# FT232-Breakout-v1.net
KiCad netlist of a schematic drawn in EAGLE
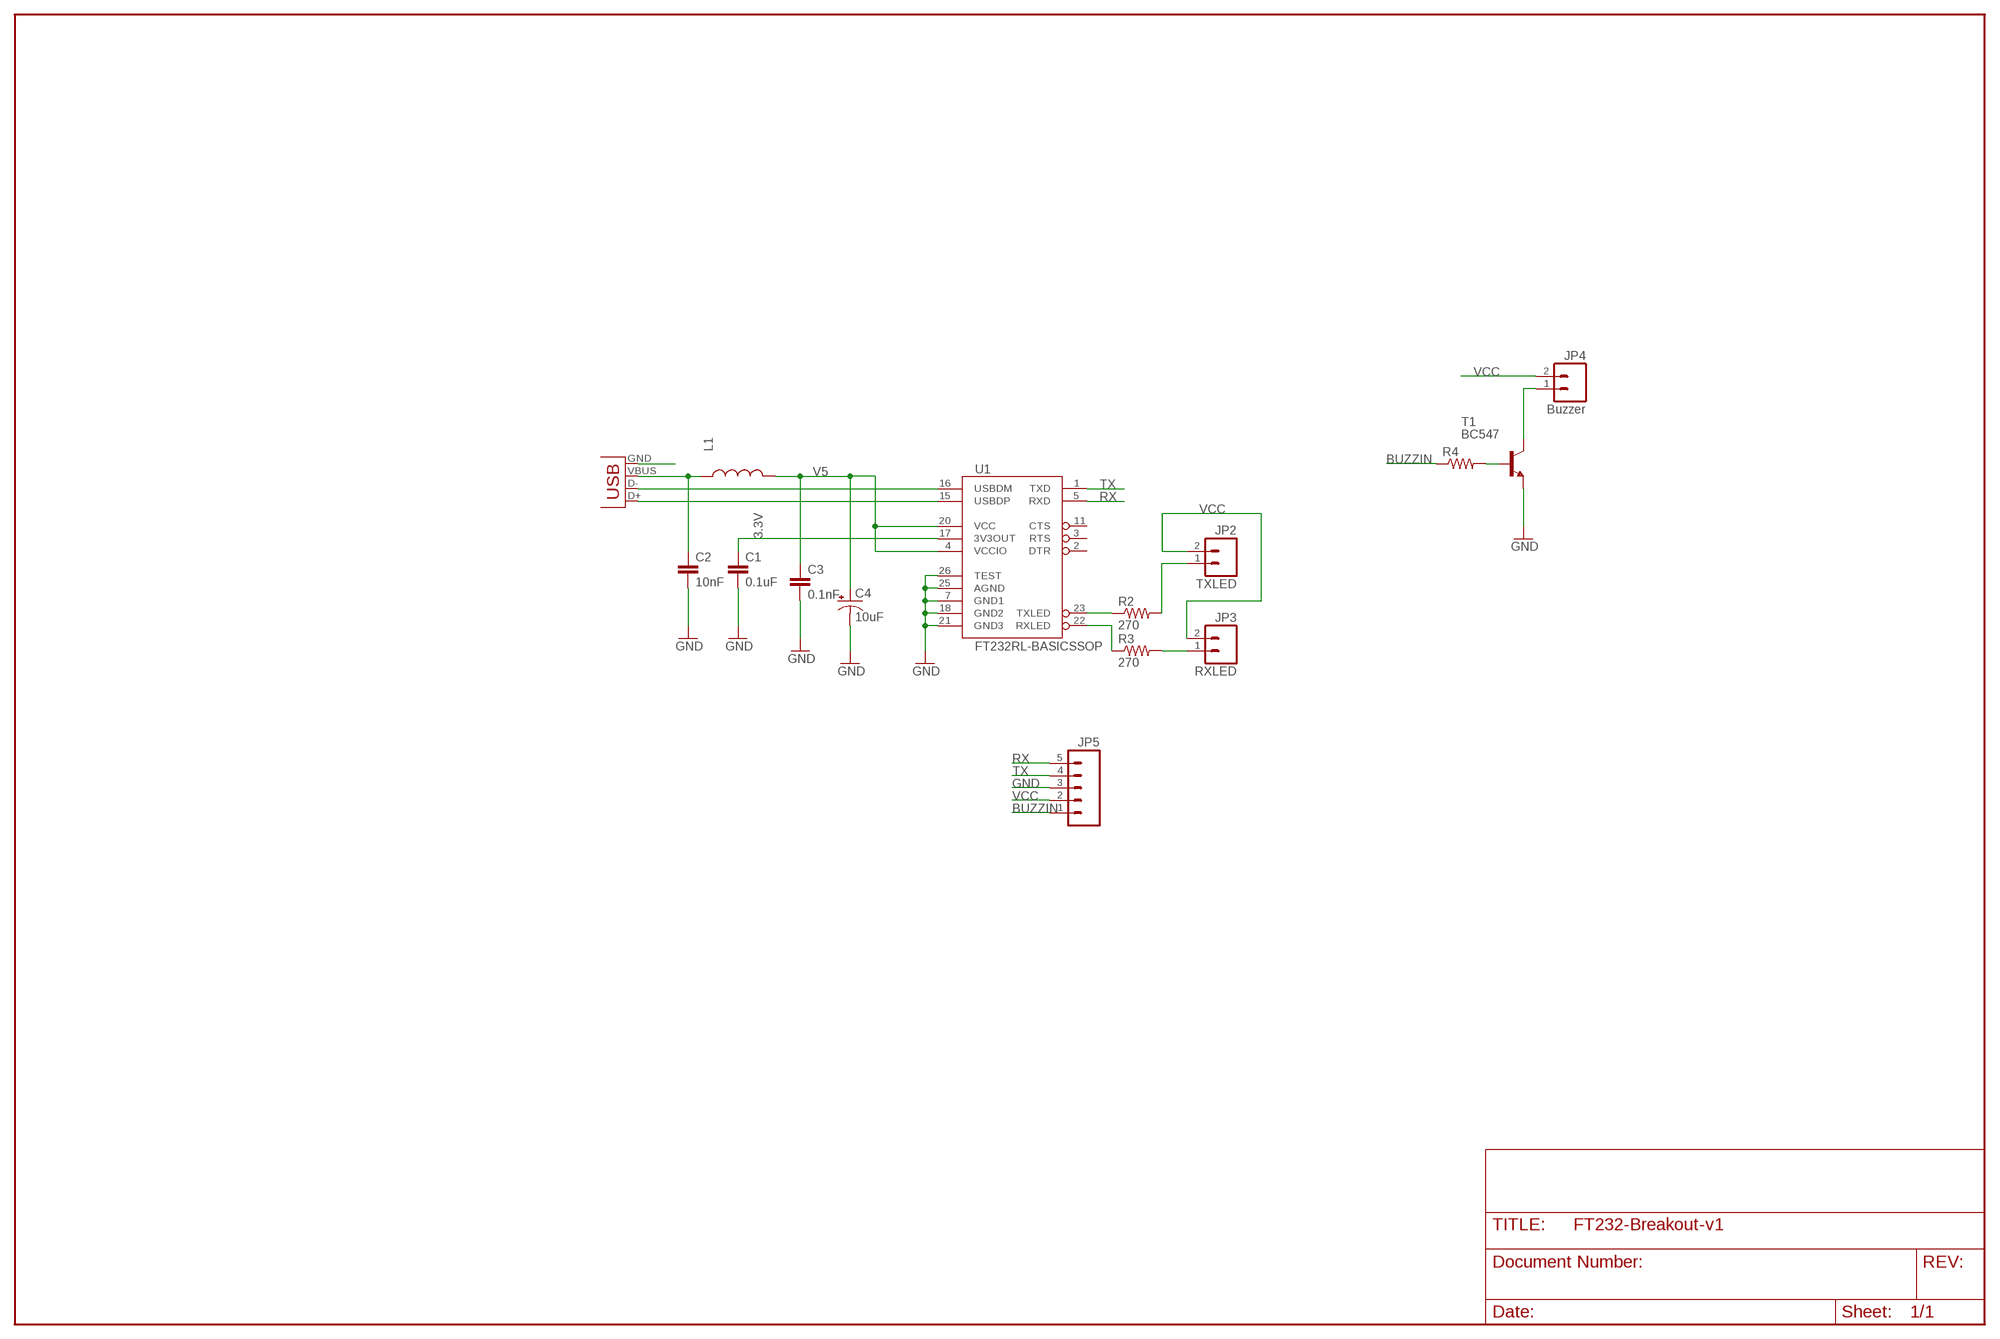
[diagram p0: schematic, sheet 1]

(export (version "E")
  (design (tool "Eeschema 10.0.6"))
  (components
    (comp (ref "C1")
      (value "0.1uF")
      (footprint "eagle-import:0402-CAP")
      (libsource (lib "eagle-import") (part ".22UF-CER"))
    )
    (comp (ref "C2")
      (value "10nF")
      (footprint "eagle-import:0402-CAP")
      (libsource (lib "eagle-import") (part ".22UF-CER"))
    )
    (comp (ref "C3")
      (value "0.1nF")
      (footprint "eagle-import:0402-CAP")
      (libsource (lib "eagle-import") (part ".22UF-CER"))
    )
    (comp (ref "C4")
      (value "10uF")
      (footprint "eagle-import:EIA3216")
      (libsource (lib "eagle-import") (part "10UF-TANT"))
    )
    (comp (ref "JP1")
      (value "USB-B")
      (footprint "eagle-import:USB-B-PTH")
      (libsource (lib "eagle-import") (part "USBPTH"))
    )
    (comp (ref "JP2")
      (value "TXLED")
      (footprint "eagle-import:1X02_LOCK")
      (libsource (lib "eagle-import") (part "M02LOCK"))
    )
    (comp (ref "JP3")
      (value "RXLED")
      (footprint "eagle-import:1X02_LOCK")
      (libsource (lib "eagle-import") (part "M02LOCK"))
    )
    (comp (ref "JP4")
      (value "Buzzer")
      (footprint "eagle-import:1X02_LOCK")
      (libsource (lib "eagle-import") (part "M02LOCK"))
    )
    (comp (ref "JP5")
      (value "M05LOCK")
      (footprint "eagle-import:1X05_LOCK")
      (libsource (lib "eagle-import") (part "M05LOCK"))
    )
    (comp (ref "L1")
      (value "INDUCTOR0603")
      (footprint "eagle-import:0603")
      (libsource (lib "eagle-import") (part "INDUCTOR0603"))
    )
    (comp (ref "R2")
      (value "270")
      (footprint "eagle-import:AXIAL-0.5")
      (libsource (lib "eagle-import") (part "RESISTORPTH-1/2W"))
    )
    (comp (ref "R3")
      (value "270")
      (footprint "eagle-import:AXIAL-0.5")
      (libsource (lib "eagle-import") (part "RESISTORPTH-1/2W"))
    )
    (comp (ref "R4")
      (value "RESISTORPTH-1/2W")
      (footprint "eagle-import:AXIAL-0.5")
      (libsource (lib "eagle-import") (part "RESISTORPTH-1/2W"))
    )
    (comp (ref "T1")
      (value "BC547")
      (footprint "eagle-import:TO92")
      (libsource (lib "eagle-import") (part "BC547"))
    )
    (comp (ref "U1")
      (value "FT232RL-BASICSSOP")
      (footprint "eagle-import:SSOP28DB")
      (libsource (lib "eagle-import") (part "FT232RL-BASICSSOP"))
    )
  )
  (nets
    (net (code "1") (name "/3.3V") (class "Default")
      (node (ref "C1") (pin "1") (pinfunction "1_1") (pintype "passive"))
      (node (ref "U1") (pin "17") (pinfunction "3V3OUT_17") (pintype "output"))
    )
    (net (code "2") (name "/BUZZIN") (class "Default")
      (node (ref "JP5") (pin "1") (pinfunction "1_1") (pintype "passive"))
      (node (ref "R4") (pin "P$1") (pinfunction "1_P$1") (pintype "passive"))
    )
    (net (code "3") (name "/RX") (class "Default")
      (node (ref "JP5") (pin "5") (pinfunction "5_5") (pintype "passive"))
      (node (ref "U1") (pin "5") (pinfunction "RXD_5") (pintype "input"))
    )
    (net (code "4") (name "/TX") (class "Default")
      (node (ref "JP5") (pin "4") (pinfunction "4_4") (pintype "passive"))
      (node (ref "U1") (pin "1") (pinfunction "TXD_1") (pintype "output"))
    )
    (net (code "5") (name "/V5") (class "Default")
      (node (ref "C3") (pin "1") (pinfunction "1_1") (pintype "passive"))
      (node (ref "C4") (pin "A") (pinfunction "+_A") (pintype "passive"))
      (node (ref "L1") (pin "2") (pinfunction "2_2") (pintype "passive"))
      (node (ref "U1") (pin "20") (pinfunction "VCC_20") (pintype "power_in"))
      (node (ref "U1") (pin "4") (pinfunction "VCCIO_4") (pintype "power_in"))
    )
    (net (code "6") (name "/VCC") (class "Default")
      (node (ref "JP2") (pin "2") (pinfunction "2_2") (pintype "passive"))
      (node (ref "JP3") (pin "2") (pinfunction "2_2") (pintype "passive"))
      (node (ref "JP4") (pin "2") (pinfunction "2_2") (pintype "passive"))
      (node (ref "JP5") (pin "2") (pinfunction "2_2") (pintype "passive"))
    )
    (net (code "7") (name "GND") (class "Default")
      (node (ref "C1") (pin "2") (pinfunction "2_2") (pintype "passive"))
      (node (ref "C2") (pin "2") (pinfunction "2_2") (pintype "passive"))
      (node (ref "C3") (pin "2") (pinfunction "2_2") (pintype "passive"))
      (node (ref "C4") (pin "C") (pinfunction "-_C") (pintype "passive"))
      (node (ref "JP1") (pin "GND") (pinfunction "GND_GND") (pintype "bidirectional"))
      (node (ref "JP5") (pin "3") (pinfunction "3_3") (pintype "passive"))
      (node (ref "T1") (pin "1") (pinfunction "E_1") (pintype "passive"))
      (node (ref "U1") (pin "18") (pinfunction "GND2_18") (pintype "power_in"))
      (node (ref "U1") (pin "21") (pinfunction "GND3_21") (pintype "power_in"))
      (node (ref "U1") (pin "25") (pinfunction "AGND_25") (pintype "power_in"))
      (node (ref "U1") (pin "26") (pinfunction "TEST_26") (pintype "input"))
      (node (ref "U1") (pin "7") (pinfunction "GND1_7") (pintype "power_in"))
    )
    (net (code "8") (name "Net-(C2-Pad1)") (class "Default")
      (node (ref "C2") (pin "1") (pinfunction "1_1") (pintype "passive"))
      (node (ref "JP1") (pin "VBUS") (pinfunction "VBUS_VBUS") (pintype "bidirectional"))
      (node (ref "L1") (pin "1") (pinfunction "1_1") (pintype "passive"))
    )
    (net (code "9") (name "Net-(R2-1)") (class "Default")
      (node (ref "R2") (pin "P$1") (pinfunction "1_P$1") (pintype "passive"))
      (node (ref "U1") (pin "23") (pinfunction "TXLED_23") (pintype "bidirectional"))
    )
    (net (code "10") (name "Net-(R2-2)") (class "Default")
      (node (ref "JP2") (pin "1") (pinfunction "1_1") (pintype "passive"))
      (node (ref "R2") (pin "P$2") (pinfunction "2_P$2") (pintype "passive"))
    )
    (net (code "11") (name "Net-(R3-1)") (class "Default")
      (node (ref "R3") (pin "P$1") (pinfunction "1_P$1") (pintype "passive"))
      (node (ref "U1") (pin "22") (pinfunction "RXLED_22") (pintype "bidirectional"))
    )
    (net (code "12") (name "Net-(R3-2)") (class "Default")
      (node (ref "JP3") (pin "1") (pinfunction "1_1") (pintype "passive"))
      (node (ref "R3") (pin "P$2") (pinfunction "2_P$2") (pintype "passive"))
    )
    (net (code "13") (name "Net-(R4-2)") (class "Default")
      (node (ref "R4") (pin "P$2") (pinfunction "2_P$2") (pintype "passive"))
      (node (ref "T1") (pin "2") (pinfunction "B_2") (pintype "passive"))
    )
    (net (code "14") (name "Net-(T1-C)") (class "Default")
      (node (ref "JP4") (pin "1") (pinfunction "1_1") (pintype "passive"))
      (node (ref "T1") (pin "3") (pinfunction "C_3") (pintype "passive"))
    )
    (net (code "15") (name "Net-(U1-USBDM)") (class "Default")
      (node (ref "JP1") (pin "D-") (pinfunction "D-_D-") (pintype "bidirectional"))
      (node (ref "U1") (pin "16") (pinfunction "USBDM_16") (pintype "bidirectional"))
    )
    (net (code "16") (name "Net-(U1-USBDP)") (class "Default")
      (node (ref "JP1") (pin "D+") (pinfunction "D+_D+") (pintype "bidirectional"))
      (node (ref "U1") (pin "15") (pinfunction "USBDP_15") (pintype "bidirectional"))
    )
    (net (code "17") (name "unconnected-(U1-CTS-Pad11)") (class "Default")
      (node (ref "U1") (pin "11") (pinfunction "CTS_11") (pintype "bidirectional"))
    )
    (net (code "18") (name "unconnected-(U1-DTR-Pad2)") (class "Default")
      (node (ref "U1") (pin "2") (pinfunction "DTR_2") (pintype "bidirectional"))
    )
    (net (code "19") (name "unconnected-(U1-RTS-Pad3)") (class "Default")
      (node (ref "U1") (pin "3") (pinfunction "RTS_3") (pintype "bidirectional"))
    )
  )
)
